# SchemaBloc.net
KiCad netlist of a schematic drawn in Altium Designer
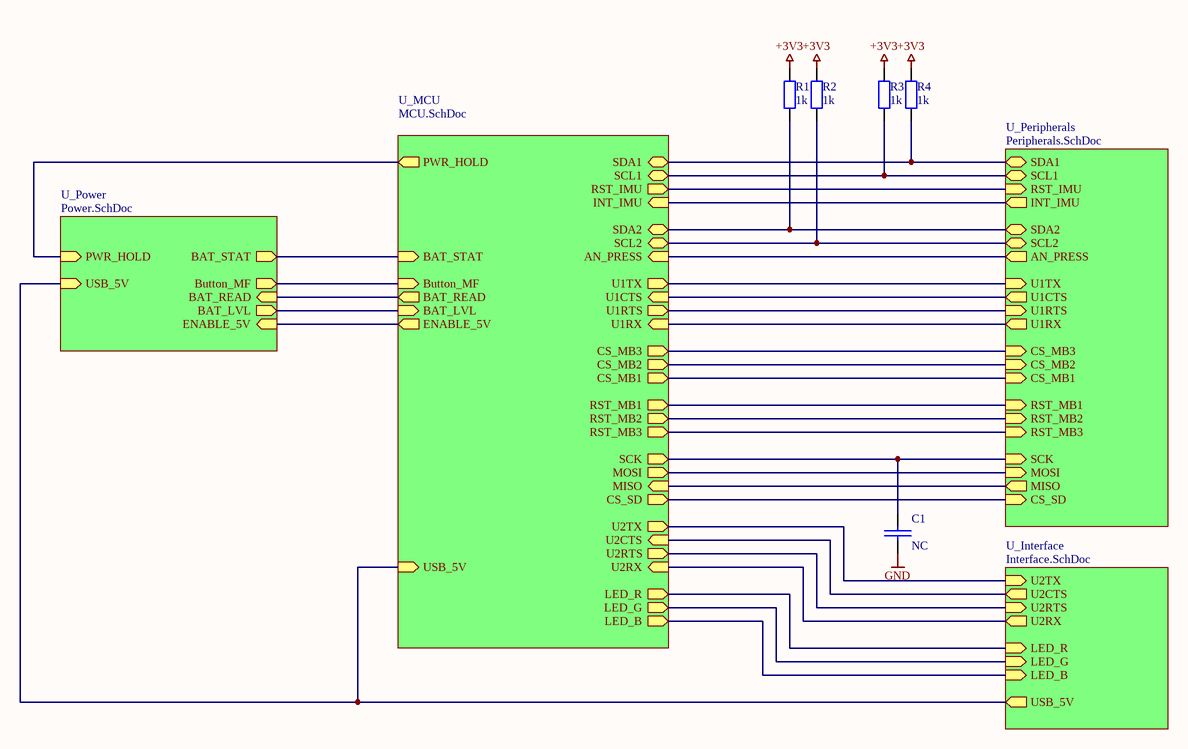
[diagram p0: SchemaBloc.SchDoc]

(export (version "E")
  (design (tool "Eeschema 10.0.6"))
  (components
    (comp (ref "C1") (value "NC") (footprint "6-0805_L") (libsource (lib "*") (part "C")))
    (comp (ref "R1")
      (value "1k")
      (footprint "6-0805_L")
      (description "Res 0805")
      (fields (field (name "PUBLISHER") "Altium Limited"))
      (libsource (lib "Miscellaneous Devices") (part "Res2"))
    )
    (comp (ref "R2")
      (value "1k")
      (footprint "6-0805_L")
      (description "Res 0805")
      (fields (field (name "PUBLISHER") "Altium Limited"))
      (libsource (lib "Miscellaneous Devices") (part "Res2"))
    )
    (comp (ref "R3")
      (value "1k")
      (footprint "6-0805_L")
      (description "Res 0805")
      (fields (field (name "PUBLISHER") "Altium Limited"))
      (libsource (lib "Miscellaneous Devices") (part "Res2"))
    )
    (comp (ref "R4")
      (value "1k")
      (footprint "6-0805_L")
      (description "Res 0805")
      (fields (field (name "PUBLISHER") "Altium Limited"))
      (libsource (lib "Miscellaneous Devices") (part "Res2"))
    )
  )
  (nets
    (net (code "1") (name "+3V3") (class "Default")
      (node (ref "R1") (pin "2") (pinfunction "2_2") (pintype "passive"))
      (node (ref "R2") (pin "2") (pinfunction "2_2") (pintype "passive"))
      (node (ref "R3") (pin "2") (pinfunction "2_2") (pintype "passive"))
      (node (ref "R4") (pin "2") (pinfunction "2_2") (pintype "passive"))
    )
    (net (code "23") (name "/SCK") (class "Default")
      (node (ref "C1") (pin "1") (pinfunction "1_1") (pintype "passive"))
    )
    (net (code "24") (name "/SCL1") (class "Default")
      (node (ref "R3") (pin "1") (pinfunction "1_1") (pintype "passive"))
    )
    (net (code "25") (name "/SCL2") (class "Default")
      (node (ref "R2") (pin "1") (pinfunction "1_1") (pintype "passive"))
    )
    (net (code "26") (name "/SDA1") (class "Default")
      (node (ref "R4") (pin "1") (pinfunction "1_1") (pintype "passive"))
    )
    (net (code "27") (name "/SDA2") (class "Default")
      (node (ref "R1") (pin "1") (pinfunction "1_1") (pintype "passive"))
    )
    (net (code "37") (name "GND") (class "Default")
      (node (ref "C1") (pin "2") (pinfunction "2_2") (pintype "passive"))
    )
  )
)
